# SensWear_Memory.net
KiCad netlist of a schematic drawn in Altium Designer
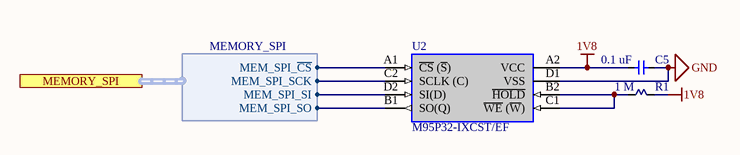
[diagram p0: SensWear_Memory.SchDoc]

(export (version "E")
  (design (tool "Eeschema 10.0.6"))
  (components
    (comp (ref "C5")
      (value "0.1 uF")
      (footprint "CAPC1005X05N")
      (description "CAP CER 0.1UF 16V X5R 0402")
      (fields
        (field (name "MANUFACTURER") "Murata Electronics")
        (field (name "MANUFACTURER PART NUMBER") "GRM155R61C104KA88D")
      )
      (libsource (lib "OpenRingComponents") (part "GRM155R61C104KA88D"))
    )
    (comp (ref "R1")
      (value "1 M")
      (footprint "RESC1005X04N")
      (description "RES SMD 1M OHM 1% 1/10W 0402")
      (fields
        (field (name "MANUFACTURER") "Panasonic Electronic Components")
        (field (name "MANUFACTURER PART NUMBER") "ERJ-2RKF1004X")
      )
      (libsource (lib "OpenRingComponents") (part "ERJ-2RKF1004X"))
    )
    (comp (ref "U2")
      (value "M95P32-IXCST/EF")
      (footprint "BGA8C70P2X4_153X261X58")
      (description "M95P32-I Series 32 Mb (4 M x 8) 80 MHz SPI EEPROM Memory IC - WLCSP-8")
      (fields (field (name "MANUFACTURER") "STMicroelectronics"))
      (libsource (lib "OpenRingComponents") (part "M95P32-IXCST/EF"))
    )
  )
  (nets
    (net (code "2") (name "/MEM_SPI_SCK") (class "Default")
      (node (ref "U2") (pin "C2") (pinfunction "SCLK_(C)_C2") (pintype "input"))
    )
    (net (code "3") (name "/MEM_SPI_SI") (class "Default")
      (node (ref "U2") (pin "D2") (pinfunction "SI(D)_D2") (pintype "input"))
    )
    (net (code "4") (name "/MEM_SPI_SO") (class "Default")
      (node (ref "U2") (pin "B1") (pinfunction "SO(Q)_B1") (pintype "output"))
    )
    (net (code "5") (name "/MEM_SPI_~{CS}") (class "Default")
      (node (ref "U2") (pin "A1") (pinfunction "~{CS}_(~{S})_A1") (pintype "input"))
    )
    (net (code "7") (name "1V8") (class "Default")
      (node (ref "C5") (pin "2") (pinfunction "2_2") (pintype "passive"))
      (node (ref "R1") (pin "2") (pinfunction "2_2") (pintype "passive"))
      (node (ref "U2") (pin "A2") (pinfunction "VCC_A2") (pintype "power_in"))
    )
    (net (code "8") (name "GND") (class "Default")
      (node (ref "C5") (pin "1") (pinfunction "1_1") (pintype "passive"))
      (node (ref "U2") (pin "D1") (pinfunction "VSS_D1") (pintype "power_in"))
    )
    (net (code "9") (name "Net-(U2-~{HOLD})") (class "Default")
      (node (ref "R1") (pin "1") (pinfunction "1_1") (pintype "passive"))
      (node (ref "U2") (pin "B2") (pinfunction "~{HOLD}_B2") (pintype "input"))
      (node (ref "U2") (pin "C1") (pinfunction "~{WE}_(~{W})_C1") (pintype "input"))
    )
  )
)
